# MRCS-Nano-Grade-Xing-Breakout.net
KiCad netlist of a schematic drawn in EAGLE
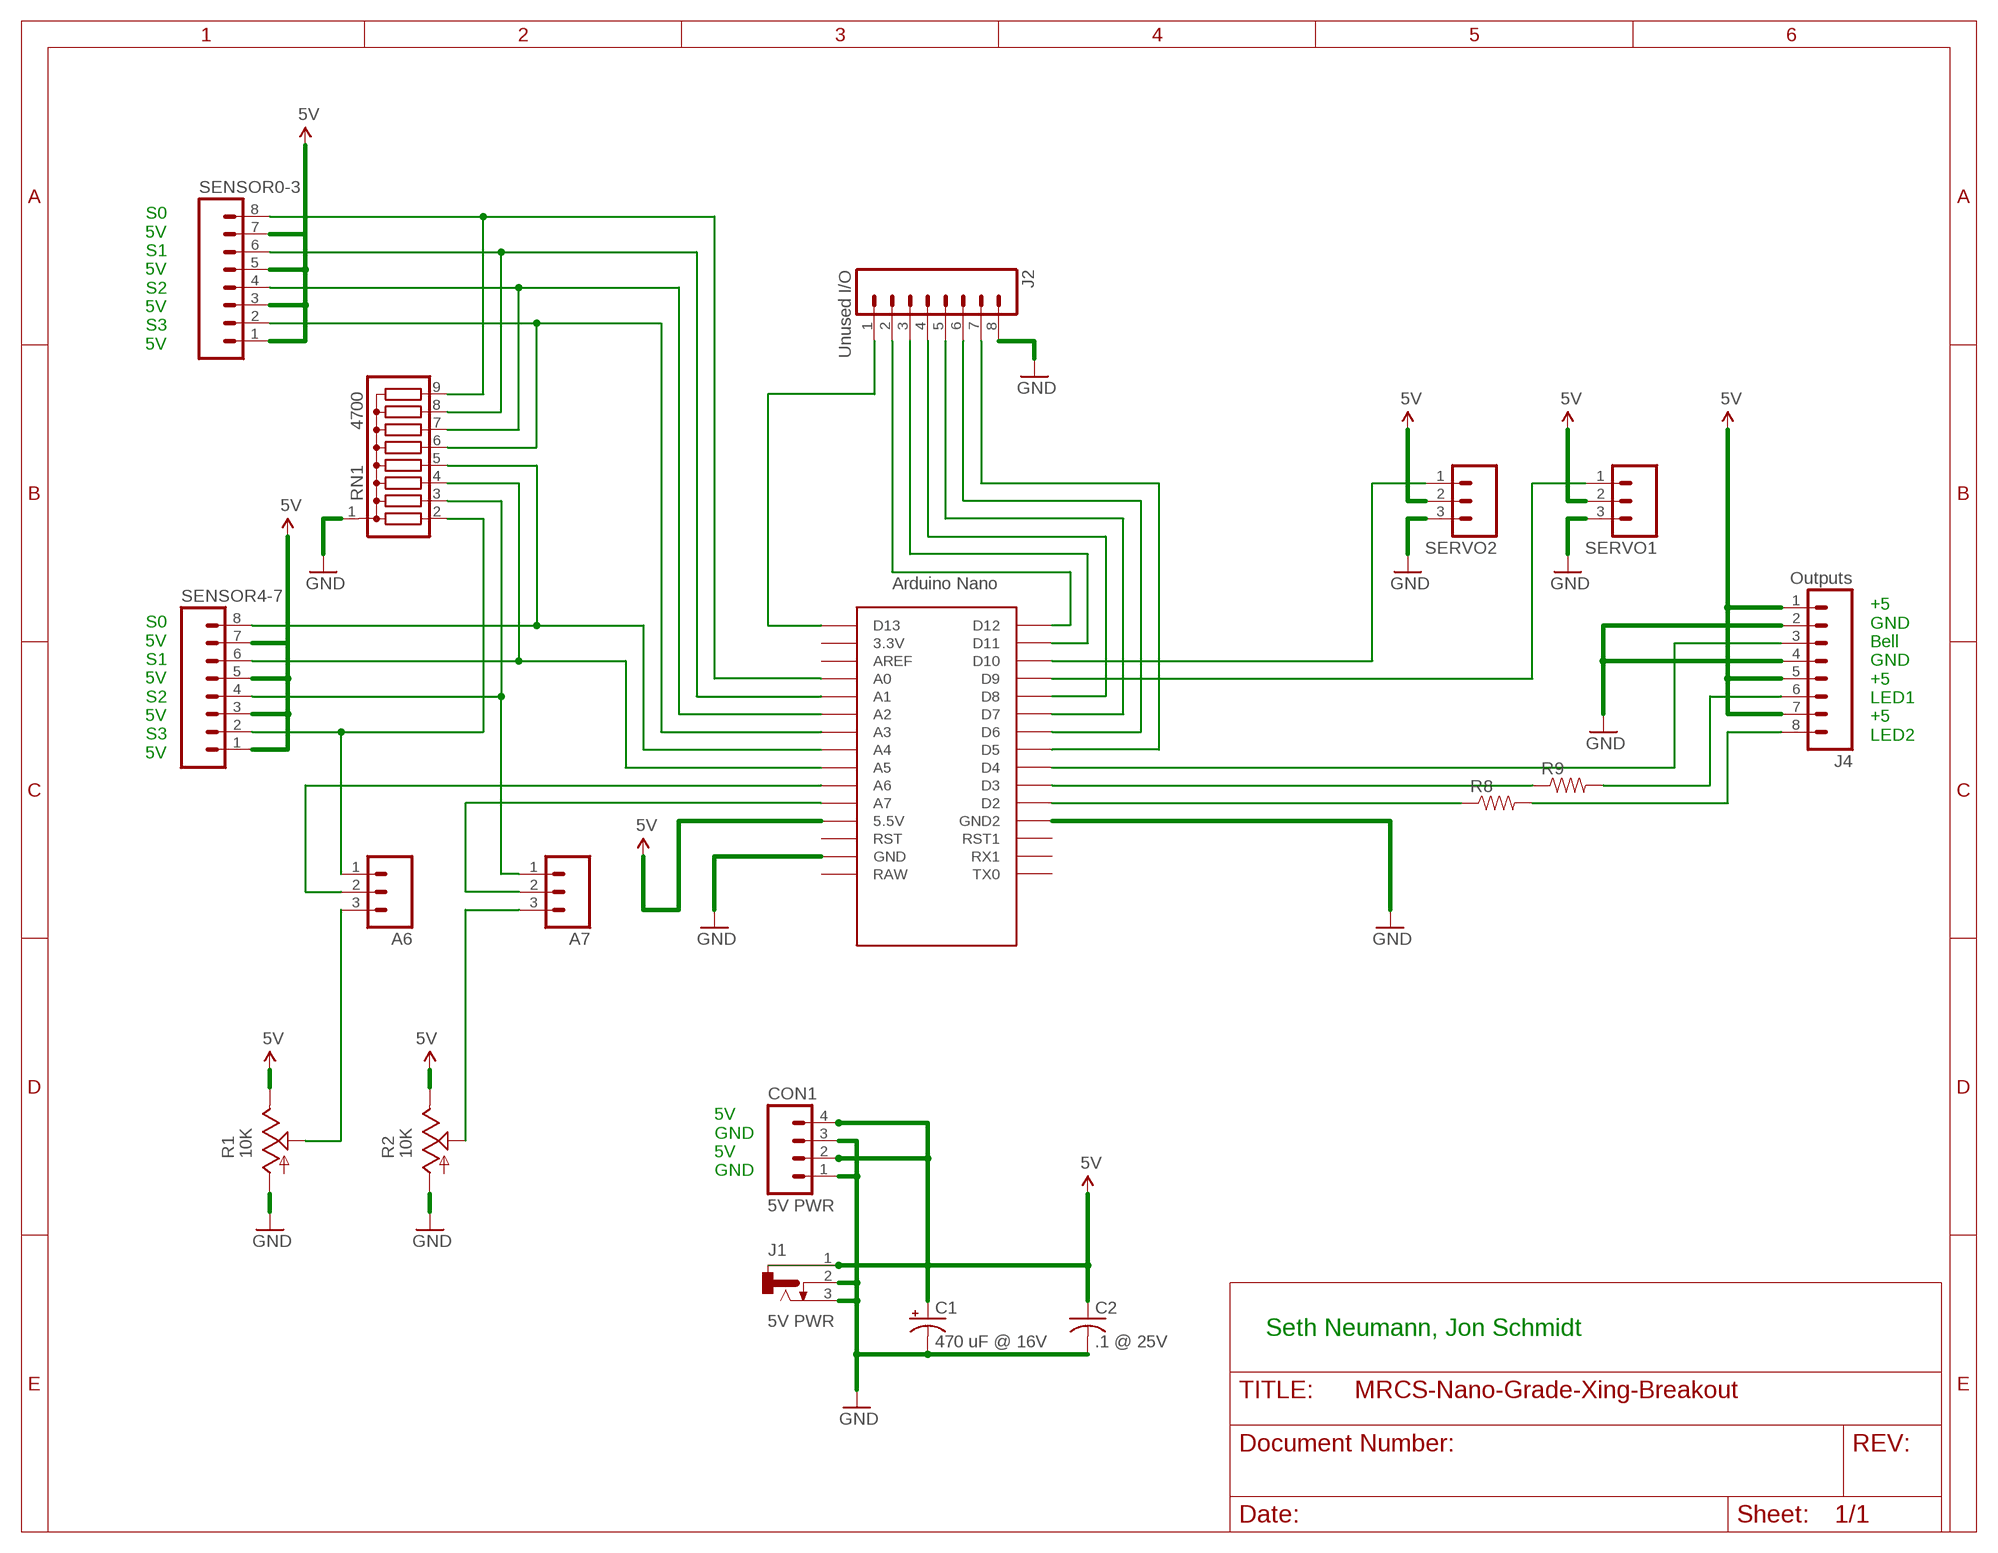
[diagram p0: schematic, sheet 1]

(export (version "E")
  (design (tool "Eeschema 10.0.6"))
  (components
    (comp (ref "A6")
      (value "M03LOCK")
      (footprint "eagle-import:1X03_LOCK")
      (libsource (lib "eagle-import") (part "M03LOCK"))
    )
    (comp (ref "A7")
      (value "M03LOCK")
      (footprint "eagle-import:1X03_LOCK")
      (libsource (lib "eagle-import") (part "M03LOCK"))
    )
    (comp (ref "C1")
      (value "470 uF @ 16V")
      (footprint "eagle-import:E3.5-10")
      (libsource (lib "eagle-import") (part "CAP-POLPTH-3.5MM"))
    )
    (comp (ref "C2")
      (value ".1 @ 25V")
      (footprint "eagle-import:C-PTH-0.100")
      (libsource (lib "eagle-import") (part "CAPPTH2"))
    )
    (comp (ref "CON1")
      (value "5V PWR")
      (footprint "eagle-import:SCREWTERMINAL-3.5MM-4_LOCK")
      (libsource (lib "eagle-import") (part "CONNECTOR-M04SCREW_LOCK"))
    )
    (comp (ref "J1")
      (value "5V PWR")
      (footprint "eagle-import:DCJ0202")
      (libsource (lib "eagle-import") (part "CONNECTOR-DC-POWER-RA"))
    )
    (comp (ref "J2")
      (value "Unused I/O")
      (footprint "eagle-import:1X08_LOCK")
      (libsource (lib "eagle-import") (part "CONNECTOR-M08LOCK"))
    )
    (comp (ref "J4")
      (value "Outputs")
      (footprint "eagle-import:1X08_LOCK")
      (libsource (lib "eagle-import") (part "CONNECTOR-M08LOCK"))
    )
    (comp (ref "R1")
      (value "10K")
      (footprint "eagle-import:RS3")
      (libsource (lib "eagle-import") (part "TRIM_US-RS3"))
    )
    (comp (ref "R2")
      (value "10K")
      (footprint "eagle-import:RS3")
      (libsource (lib "eagle-import") (part "TRIM_US-RS3"))
    )
    (comp (ref "R8")
      (value "RPTH-R0")
      (footprint "eagle-import:CUT-R")
      (libsource (lib "eagle-import") (part "RPTH-R0"))
    )
    (comp (ref "R9")
      (value "RPTH-R0")
      (footprint "eagle-import:CUT-R")
      (libsource (lib "eagle-import") (part "RPTH-R0"))
    )
    (comp (ref "RN1")
      (value "4700")
      (footprint "eagle-import:SIL9")
      (libsource (lib "eagle-import") (part "G08R"))
    )
    (comp (ref "SENSOR0-3")
      (value "CONNECTOR-M08LOCK")
      (footprint "eagle-import:1X08_LOCK")
      (libsource (lib "eagle-import") (part "CONNECTOR-M08LOCK"))
    )
    (comp (ref "SENSOR4-7")
      (value "CONNECTOR-M08LOCK")
      (footprint "eagle-import:1X08_LOCK")
      (libsource (lib "eagle-import") (part "CONNECTOR-M08LOCK"))
    )
    (comp (ref "SERVO1")
      (value "M03LOCK")
      (footprint "eagle-import:1X03_LOCK")
      (libsource (lib "eagle-import") (part "M03LOCK"))
    )
    (comp (ref "SERVO2")
      (value "M03LOCK")
      (footprint "eagle-import:1X03_LOCK")
      (libsource (lib "eagle-import") (part "M03LOCK"))
    )
    (comp (ref "U$1")
      (value "NANO")
      (footprint "eagle-import:NANO")
      (libsource (lib "eagle-import") (part "NANO"))
    )
  )
  (nets
    (net (code "1") (name "5V") (class "Default")
      (node (ref "C1") (pin "+") (pinfunction "+_+") (pintype "passive"))
      (node (ref "C2") (pin "1") (pinfunction "1_1") (pintype "passive"))
      (node (ref "CON1") (pin "2") (pinfunction "2_2") (pintype "passive"))
      (node (ref "CON1") (pin "4") (pinfunction "4_4") (pintype "passive"))
      (node (ref "J1") (pin "1") (pinfunction "1_1") (pintype "passive"))
      (node (ref "J4") (pin "1") (pinfunction "1_1") (pintype "passive"))
      (node (ref "J4") (pin "5") (pinfunction "5_5") (pintype "passive"))
      (node (ref "J4") (pin "7") (pinfunction "7_7") (pintype "passive"))
      (node (ref "R1") (pin "E") (pinfunction "E_E") (pintype "passive"))
      (node (ref "R2") (pin "E") (pinfunction "E_E") (pintype "passive"))
      (node (ref "SENSOR0-3") (pin "1") (pinfunction "1_1") (pintype "passive"))
      (node (ref "SENSOR0-3") (pin "3") (pinfunction "3_3") (pintype "passive"))
      (node (ref "SENSOR0-3") (pin "5") (pinfunction "5_5") (pintype "passive"))
      (node (ref "SENSOR0-3") (pin "7") (pinfunction "7_7") (pintype "passive"))
      (node (ref "SENSOR4-7") (pin "1") (pinfunction "1_1") (pintype "passive"))
      (node (ref "SENSOR4-7") (pin "3") (pinfunction "3_3") (pintype "passive"))
      (node (ref "SENSOR4-7") (pin "5") (pinfunction "5_5") (pintype "passive"))
      (node (ref "SENSOR4-7") (pin "7") (pinfunction "7_7") (pintype "passive"))
      (node (ref "SERVO1") (pin "2") (pinfunction "2_2") (pintype "passive"))
      (node (ref "SERVO2") (pin "2") (pinfunction "2_2") (pintype "passive"))
      (node (ref "U$1") (pin "5V") (pinfunction "5.5V_5V") (pintype "bidirectional"))
    )
    (net (code "2") (name "GND") (class "Default")
      (node (ref "C1") (pin "-") (pinfunction "-_-") (pintype "passive"))
      (node (ref "C2") (pin "2") (pinfunction "2_2") (pintype "passive"))
      (node (ref "CON1") (pin "1") (pinfunction "1_1") (pintype "passive"))
      (node (ref "CON1") (pin "3") (pinfunction "3_3") (pintype "passive"))
      (node (ref "J1") (pin "2") (pinfunction "2_2") (pintype "passive"))
      (node (ref "J1") (pin "3") (pinfunction "3_3") (pintype "passive"))
      (node (ref "J2") (pin "8") (pinfunction "8_8") (pintype "passive"))
      (node (ref "J4") (pin "2") (pinfunction "2_2") (pintype "passive"))
      (node (ref "J4") (pin "4") (pinfunction "4_4") (pintype "passive"))
      (node (ref "R1") (pin "A") (pinfunction "A_A") (pintype "passive"))
      (node (ref "R2") (pin "A") (pinfunction "A_A") (pintype "passive"))
      (node (ref "RN1") (pin "1") (pinfunction "1_1") (pintype "passive"))
      (node (ref "SERVO1") (pin "3") (pinfunction "3_3") (pintype "passive"))
      (node (ref "SERVO2") (pin "3") (pinfunction "3_3") (pintype "passive"))
      (node (ref "U$1") (pin "GND") (pinfunction "GND_GND") (pintype "bidirectional"))
      (node (ref "U$1") (pin "GND1") (pinfunction "GND2_GND1") (pintype "bidirectional"))
    )
    (net (code "3") (name "Net-(A6-Pad1)") (class "Default")
      (node (ref "A6") (pin "1") (pinfunction "1_1") (pintype "passive"))
      (node (ref "RN1") (pin "2") (pinfunction "2_2") (pintype "passive"))
      (node (ref "SENSOR4-7") (pin "2") (pinfunction "2_2") (pintype "passive"))
    )
    (net (code "4") (name "Net-(A6-Pad2)") (class "Default")
      (node (ref "A6") (pin "2") (pinfunction "2_2") (pintype "passive"))
      (node (ref "U$1") (pin "A6") (pinfunction "A6_A6") (pintype "bidirectional"))
    )
    (net (code "5") (name "Net-(A6-Pad3)") (class "Default")
      (node (ref "A6") (pin "3") (pinfunction "3_3") (pintype "passive"))
      (node (ref "R1") (pin "S") (pinfunction "S_S") (pintype "passive"))
    )
    (net (code "6") (name "Net-(A7-Pad1)") (class "Default")
      (node (ref "A7") (pin "1") (pinfunction "1_1") (pintype "passive"))
      (node (ref "RN1") (pin "3") (pinfunction "3_3") (pintype "passive"))
      (node (ref "SENSOR4-7") (pin "4") (pinfunction "4_4") (pintype "passive"))
    )
    (net (code "7") (name "Net-(A7-Pad2)") (class "Default")
      (node (ref "A7") (pin "2") (pinfunction "2_2") (pintype "passive"))
      (node (ref "U$1") (pin "A7") (pinfunction "A7_A7") (pintype "bidirectional"))
    )
    (net (code "8") (name "Net-(A7-Pad3)") (class "Default")
      (node (ref "A7") (pin "3") (pinfunction "3_3") (pintype "passive"))
      (node (ref "R2") (pin "S") (pinfunction "S_S") (pintype "passive"))
    )
    (net (code "9") (name "Net-(J2-Pad1)") (class "Default")
      (node (ref "J2") (pin "1") (pinfunction "1_1") (pintype "passive"))
      (node (ref "U$1") (pin "D13") (pinfunction "D13_D13") (pintype "bidirectional"))
    )
    (net (code "10") (name "Net-(J2-Pad2)") (class "Default")
      (node (ref "J2") (pin "2") (pinfunction "2_2") (pintype "passive"))
      (node (ref "U$1") (pin "D12") (pinfunction "D12_D12") (pintype "bidirectional"))
    )
    (net (code "11") (name "Net-(J2-Pad3)") (class "Default")
      (node (ref "J2") (pin "3") (pinfunction "3_3") (pintype "passive"))
      (node (ref "U$1") (pin "D11") (pinfunction "D11_D11") (pintype "bidirectional"))
    )
    (net (code "12") (name "Net-(J2-Pad4)") (class "Default")
      (node (ref "J2") (pin "4") (pinfunction "4_4") (pintype "passive"))
      (node (ref "U$1") (pin "D8") (pinfunction "D8_D8") (pintype "bidirectional"))
    )
    (net (code "13") (name "Net-(J2-Pad5)") (class "Default")
      (node (ref "J2") (pin "5") (pinfunction "5_5") (pintype "passive"))
      (node (ref "U$1") (pin "D7") (pinfunction "D7_D7") (pintype "bidirectional"))
    )
    (net (code "14") (name "Net-(J2-Pad6)") (class "Default")
      (node (ref "J2") (pin "6") (pinfunction "6_6") (pintype "passive"))
      (node (ref "U$1") (pin "D6") (pinfunction "D6_D6") (pintype "bidirectional"))
    )
    (net (code "15") (name "Net-(J2-Pad7)") (class "Default")
      (node (ref "J2") (pin "7") (pinfunction "7_7") (pintype "passive"))
      (node (ref "U$1") (pin "D5") (pinfunction "D5_D5") (pintype "bidirectional"))
    )
    (net (code "16") (name "Net-(J4-Pad3)") (class "Default")
      (node (ref "J4") (pin "3") (pinfunction "3_3") (pintype "passive"))
      (node (ref "U$1") (pin "D4") (pinfunction "D4_D4") (pintype "bidirectional"))
    )
    (net (code "17") (name "Net-(R8-1)") (class "Default")
      (node (ref "R8") (pin "P2") (pinfunction "1_P2") (pintype "passive"))
      (node (ref "U$1") (pin "D2") (pinfunction "D2_D2") (pintype "bidirectional"))
    )
    (net (code "18") (name "Net-(R8-2)") (class "Default")
      (node (ref "J4") (pin "8") (pinfunction "8_8") (pintype "passive"))
      (node (ref "R8") (pin "P1") (pinfunction "2_P1") (pintype "passive"))
    )
    (net (code "19") (name "Net-(R9-1)") (class "Default")
      (node (ref "R9") (pin "P2") (pinfunction "1_P2") (pintype "passive"))
      (node (ref "U$1") (pin "D3") (pinfunction "D3_D3") (pintype "bidirectional"))
    )
    (net (code "20") (name "Net-(R9-2)") (class "Default")
      (node (ref "J4") (pin "6") (pinfunction "6_6") (pintype "passive"))
      (node (ref "R9") (pin "P1") (pinfunction "2_P1") (pintype "passive"))
    )
    (net (code "21") (name "Net-(RN1-Pad4)") (class "Default")
      (node (ref "RN1") (pin "4") (pinfunction "4_4") (pintype "passive"))
      (node (ref "SENSOR4-7") (pin "6") (pinfunction "6_6") (pintype "passive"))
      (node (ref "U$1") (pin "A5") (pinfunction "A5_A5") (pintype "bidirectional"))
    )
    (net (code "22") (name "Net-(RN1-Pad5)") (class "Default")
      (node (ref "RN1") (pin "5") (pinfunction "5_5") (pintype "passive"))
      (node (ref "SENSOR4-7") (pin "8") (pinfunction "8_8") (pintype "passive"))
      (node (ref "U$1") (pin "A4") (pinfunction "A4_A4") (pintype "bidirectional"))
    )
    (net (code "23") (name "Net-(RN1-Pad6)") (class "Default")
      (node (ref "RN1") (pin "6") (pinfunction "6_6") (pintype "passive"))
      (node (ref "SENSOR0-3") (pin "2") (pinfunction "2_2") (pintype "passive"))
      (node (ref "U$1") (pin "A3") (pinfunction "A3_A3") (pintype "bidirectional"))
    )
    (net (code "24") (name "Net-(RN1-Pad7)") (class "Default")
      (node (ref "RN1") (pin "7") (pinfunction "7_7") (pintype "passive"))
      (node (ref "SENSOR0-3") (pin "4") (pinfunction "4_4") (pintype "passive"))
      (node (ref "U$1") (pin "A2") (pinfunction "A2_A2") (pintype "bidirectional"))
    )
    (net (code "25") (name "Net-(RN1-Pad8)") (class "Default")
      (node (ref "RN1") (pin "8") (pinfunction "8_8") (pintype "passive"))
      (node (ref "SENSOR0-3") (pin "6") (pinfunction "6_6") (pintype "passive"))
      (node (ref "U$1") (pin "A1") (pinfunction "A1_A1") (pintype "bidirectional"))
    )
    (net (code "26") (name "Net-(RN1-Pad9)") (class "Default")
      (node (ref "RN1") (pin "9") (pinfunction "9_9") (pintype "passive"))
      (node (ref "SENSOR0-3") (pin "8") (pinfunction "8_8") (pintype "passive"))
      (node (ref "U$1") (pin "A0") (pinfunction "A0_A0") (pintype "bidirectional"))
    )
    (net (code "27") (name "Net-(SERVO1-Pad1)") (class "Default")
      (node (ref "SERVO1") (pin "1") (pinfunction "1_1") (pintype "passive"))
      (node (ref "U$1") (pin "D9") (pinfunction "D9_D9") (pintype "bidirectional"))
    )
    (net (code "28") (name "Net-(SERVO2-Pad1)") (class "Default")
      (node (ref "SERVO2") (pin "1") (pinfunction "1_1") (pintype "passive"))
      (node (ref "U$1") (pin "D10") (pinfunction "D10_D10") (pintype "bidirectional"))
    )
    (net (code "29") (name "unconnected-(U$1-Pad3.3V)") (class "Default")
      (node (ref "U$1") (pin "3.3V") (pinfunction "3.3V_3.3V") (pintype "bidirectional"))
    )
    (net (code "30") (name "unconnected-(U$1-PadAREF)") (class "Default")
      (node (ref "U$1") (pin "AREF") (pinfunction "AREF_AREF") (pintype "bidirectional"))
    )
    (net (code "31") (name "unconnected-(U$1-PadRAW)") (class "Default")
      (node (ref "U$1") (pin "RAW") (pinfunction "RAW_RAW") (pintype "bidirectional"))
    )
    (net (code "32") (name "unconnected-(U$1-PadRST)") (class "Default")
      (node (ref "U$1") (pin "RST") (pinfunction "RST_RST") (pintype "bidirectional"))
    )
    (net (code "33") (name "unconnected-(U$1-PadRST1)") (class "Default")
      (node (ref "U$1") (pin "RST1") (pinfunction "RST1_RST1") (pintype "bidirectional"))
    )
    (net (code "34") (name "unconnected-(U$1-PadRX1)") (class "Default")
      (node (ref "U$1") (pin "RX1") (pinfunction "RX1_RX1") (pintype "bidirectional"))
    )
    (net (code "35") (name "unconnected-(U$1-PadTX0)") (class "Default")
      (node (ref "U$1") (pin "TX0") (pinfunction "TX0_TX0") (pintype "bidirectional"))
    )
  )
)
